# mailbox_schematic.net
KiCad netlist of a schematic drawn in EAGLE
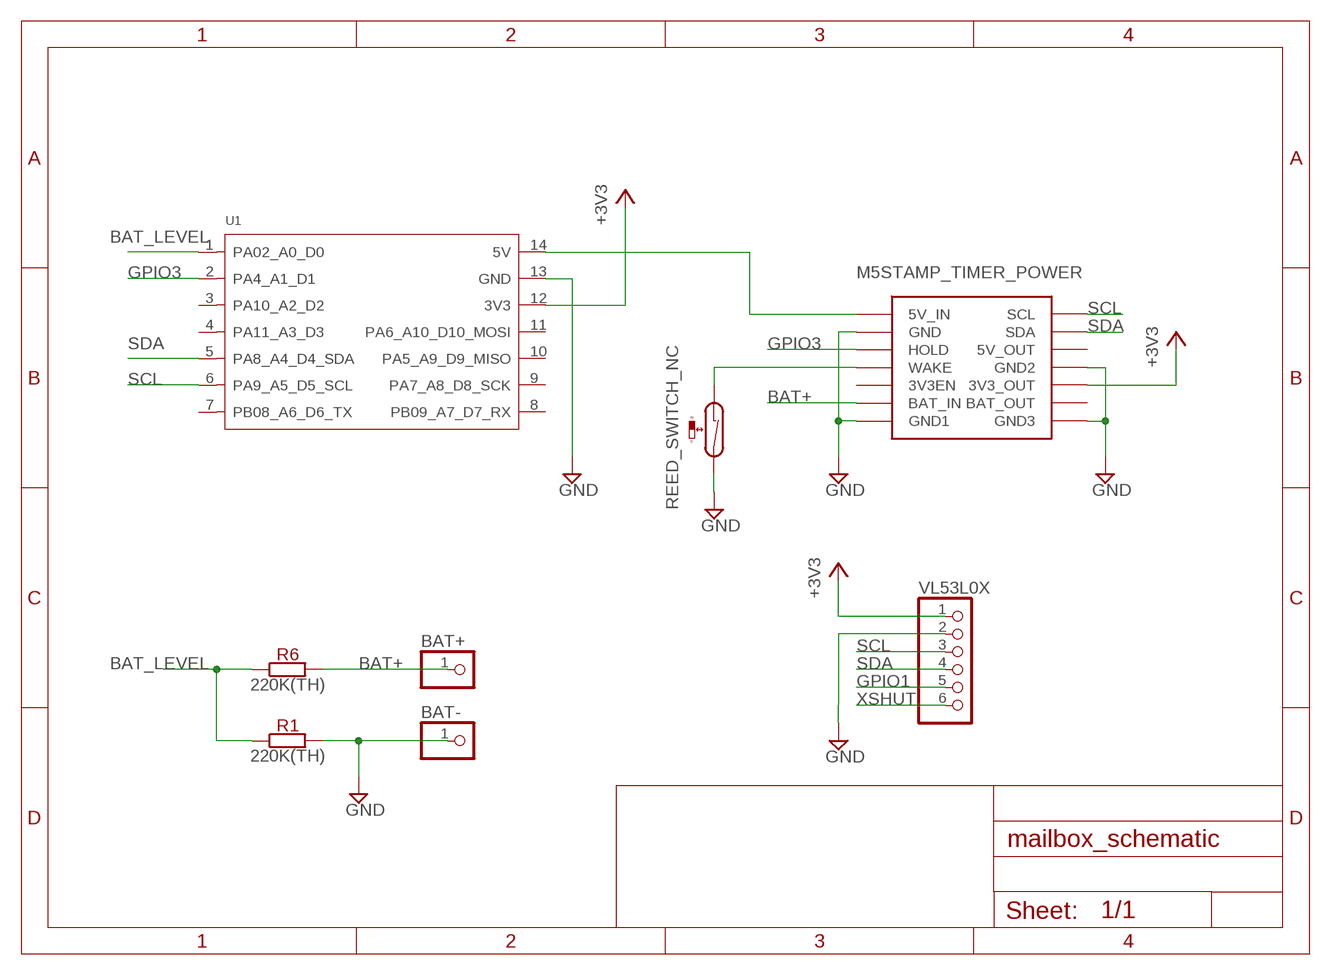
[diagram p0: schematic, sheet 1]

(export (version "E")
  (design (tool "Eeschema 10.0.6"))
  (components
    (comp (ref "BAT+")
      (value "PINHD-1X1")
      (footprint "eagle-import:1X01")
      (libsource (lib "eagle-import") (part "PINHD-1X1"))
    )
    (comp (ref "BAT-")
      (value "PINHD-1X1")
      (footprint "eagle-import:1X01")
      (libsource (lib "eagle-import") (part "PINHD-1X1"))
    )
    (comp (ref "M5STAMP_TIMER_POWER")
      (value "M5STAMP_TIMER_POWER")
      (footprint "eagle-import:M5STAMP_TIMER_POWER")
      (libsource (lib "eagle-import") (part "M5STAMP_TIMER_POWER"))
    )
    (comp (ref "R1")
      (value "220K(TH)")
      (footprint "eagle-import:R-0207_10")
      (libsource (lib "eagle-import") (part "?220K(TH)"))
    )
    (comp (ref "R6")
      (value "220K(TH)")
      (footprint "eagle-import:R-0207_10")
      (libsource (lib "eagle-import") (part "?220K(TH)"))
    )
    (comp (ref "S1")
      (value "REED_SWITCH_NC")
      (footprint "eagle-import:MK6-4")
      (libsource (lib "eagle-import") (part "REED-SWITCH-MK6-4"))
    )
    (comp (ref "U1")
      (value "MOUDLE-SEEEDUINO-XIAO-ESP32C3THT")
      (footprint "eagle-import:MOUDLE14P-2.54-21X17.8MM")
      (libsource (lib "eagle-import") (part "MOUDLE-SEEEDUINO-XIAO-ESP32C3THT"))
    )
    (comp (ref "VL53L0X")
      (value "PINHD-1X06_2.54")
      (footprint "eagle-import:1X06")
      (libsource (lib "eagle-import") (part "PINHD-1X06_2.54"))
    )
  )
  (nets
    (net (code "1") (name "+3V3") (class "Default")
      (node (ref "M5STAMP_TIMER_POWER") (pin "3V3_OUT") (pinfunction "3V3_OUT_3V3_OUT") (pintype "bidirectional"))
      (node (ref "U1") (pin "12") (pinfunction "3V3_12") (pintype "bidirectional"))
      (node (ref "VL53L0X") (pin "1") (pinfunction "1_1") (pintype "passive"))
    )
    (net (code "2") (name "/BAT+") (class "Default")
      (node (ref "BAT+") (pin "1") (pinfunction "1_1") (pintype "passive"))
      (node (ref "M5STAMP_TIMER_POWER") (pin "BAT_IN") (pinfunction "BAT_IN_BAT_IN") (pintype "bidirectional"))
      (node (ref "R6") (pin "2") (pinfunction "2_2") (pintype "passive"))
    )
    (net (code "3") (name "/BAT_LEVEL") (class "Default")
      (node (ref "R1") (pin "1") (pinfunction "1_1") (pintype "passive"))
      (node (ref "R6") (pin "1") (pinfunction "1_1") (pintype "passive"))
      (node (ref "U1") (pin "1") (pinfunction "PA02_A0_D0_1") (pintype "bidirectional"))
    )
    (net (code "4") (name "/GPIO1") (class "Default")
      (node (ref "VL53L0X") (pin "5") (pinfunction "5_5") (pintype "passive"))
    )
    (net (code "5") (name "/GPIO3") (class "Default")
      (node (ref "M5STAMP_TIMER_POWER") (pin "HOLD") (pinfunction "HOLD_HOLD") (pintype "bidirectional"))
      (node (ref "U1") (pin "2") (pinfunction "PA4_A1_D1_2") (pintype "bidirectional"))
    )
    (net (code "6") (name "/SCL") (class "Default")
      (node (ref "M5STAMP_TIMER_POWER") (pin "SCL") (pinfunction "SCL_SCL") (pintype "bidirectional"))
      (node (ref "U1") (pin "6") (pinfunction "PA9_A5_D5_SCL_6") (pintype "bidirectional"))
      (node (ref "VL53L0X") (pin "3") (pinfunction "3_3") (pintype "passive"))
    )
    (net (code "7") (name "/SDA") (class "Default")
      (node (ref "M5STAMP_TIMER_POWER") (pin "SDA") (pinfunction "SDA_SDA") (pintype "bidirectional"))
      (node (ref "U1") (pin "5") (pinfunction "PA8_A4_D4_SDA_5") (pintype "bidirectional"))
      (node (ref "VL53L0X") (pin "4") (pinfunction "4_4") (pintype "passive"))
    )
    (net (code "8") (name "/XSHUT") (class "Default")
      (node (ref "VL53L0X") (pin "6") (pinfunction "6_6") (pintype "passive"))
    )
    (net (code "9") (name "GND") (class "Default")
      (node (ref "BAT-") (pin "1") (pinfunction "1_1") (pintype "passive"))
      (node (ref "M5STAMP_TIMER_POWER") (pin "GND") (pinfunction "GND_GND") (pintype "bidirectional"))
      (node (ref "M5STAMP_TIMER_POWER") (pin "GND1") (pinfunction "GND1_GND1") (pintype "bidirectional"))
      (node (ref "M5STAMP_TIMER_POWER") (pin "GND2") (pinfunction "GND2_GND2") (pintype "bidirectional"))
      (node (ref "M5STAMP_TIMER_POWER") (pin "GND3") (pinfunction "GND3_GND3") (pintype "bidirectional"))
      (node (ref "R1") (pin "2") (pinfunction "2_2") (pintype "passive"))
      (node (ref "S1") (pin "2") (pinfunction "2_2") (pintype "passive"))
      (node (ref "U1") (pin "13") (pinfunction "GND_13") (pintype "bidirectional"))
      (node (ref "VL53L0X") (pin "2") (pinfunction "2_2") (pintype "passive"))
    )
    (net (code "10") (name "Net-(M5STAMP_TIMER_POWER-PadWAKE)") (class "Default")
      (node (ref "M5STAMP_TIMER_POWER") (pin "WAKE") (pinfunction "WAKE_WAKE") (pintype "bidirectional"))
      (node (ref "S1") (pin "1") (pinfunction "1_1") (pintype "passive"))
    )
    (net (code "11") (name "Net-(U1-5V)") (class "Default")
      (node (ref "M5STAMP_TIMER_POWER") (pin "5V_IN") (pinfunction "5V_IN_5V_IN") (pintype "bidirectional"))
      (node (ref "U1") (pin "14") (pinfunction "5V_14") (pintype "bidirectional"))
    )
    (net (code "12") (name "unconnected-(M5STAMP_TIMER_POWER-Pad3V3EN)") (class "Default")
      (node (ref "M5STAMP_TIMER_POWER") (pin "3V3EN") (pinfunction "3V3EN_3V3EN") (pintype "bidirectional"))
    )
    (net (code "13") (name "unconnected-(M5STAMP_TIMER_POWER-Pad5V_OUT)") (class "Default")
      (node (ref "M5STAMP_TIMER_POWER") (pin "5V_OUT") (pinfunction "5V_OUT_5V_OUT") (pintype "bidirectional"))
    )
    (net (code "14") (name "unconnected-(M5STAMP_TIMER_POWER-PadBAT_OUT)") (class "Default")
      (node (ref "M5STAMP_TIMER_POWER") (pin "BAT_OUT") (pinfunction "BAT_OUT_BAT_OUT") (pintype "bidirectional"))
    )
    (net (code "15") (name "unconnected-(U1-PA5_A9_D9_MISO-Pad10)") (class "Default")
      (node (ref "U1") (pin "10") (pinfunction "PA5_A9_D9_MISO_10") (pintype "bidirectional"))
    )
    (net (code "16") (name "unconnected-(U1-PA6_A10_D10_MOSI-Pad11)") (class "Default")
      (node (ref "U1") (pin "11") (pinfunction "PA6_A10_D10_MOSI_11") (pintype "bidirectional"))
    )
    (net (code "17") (name "unconnected-(U1-PA7_A8_D8_SCK-Pad9)") (class "Default")
      (node (ref "U1") (pin "9") (pinfunction "PA7_A8_D8_SCK_9") (pintype "bidirectional"))
    )
    (net (code "18") (name "unconnected-(U1-PA10_A2_D2-Pad3)") (class "Default")
      (node (ref "U1") (pin "3") (pinfunction "PA10_A2_D2_3") (pintype "bidirectional"))
    )
    (net (code "19") (name "unconnected-(U1-PA11_A3_D3-Pad4)") (class "Default")
      (node (ref "U1") (pin "4") (pinfunction "PA11_A3_D3_4") (pintype "bidirectional"))
    )
    (net (code "20") (name "unconnected-(U1-PB08_A6_D6_TX-Pad7)") (class "Default")
      (node (ref "U1") (pin "7") (pinfunction "PB08_A6_D6_TX_7") (pintype "bidirectional"))
    )
    (net (code "21") (name "unconnected-(U1-PB09_A7_D7_RX-Pad8)") (class "Default")
      (node (ref "U1") (pin "8") (pinfunction "PB09_A7_D7_RX_8") (pintype "bidirectional"))
    )
  )
)
